# Adafruit_7seg_backpack.net
KiCad netlist of a schematic drawn in EAGLE
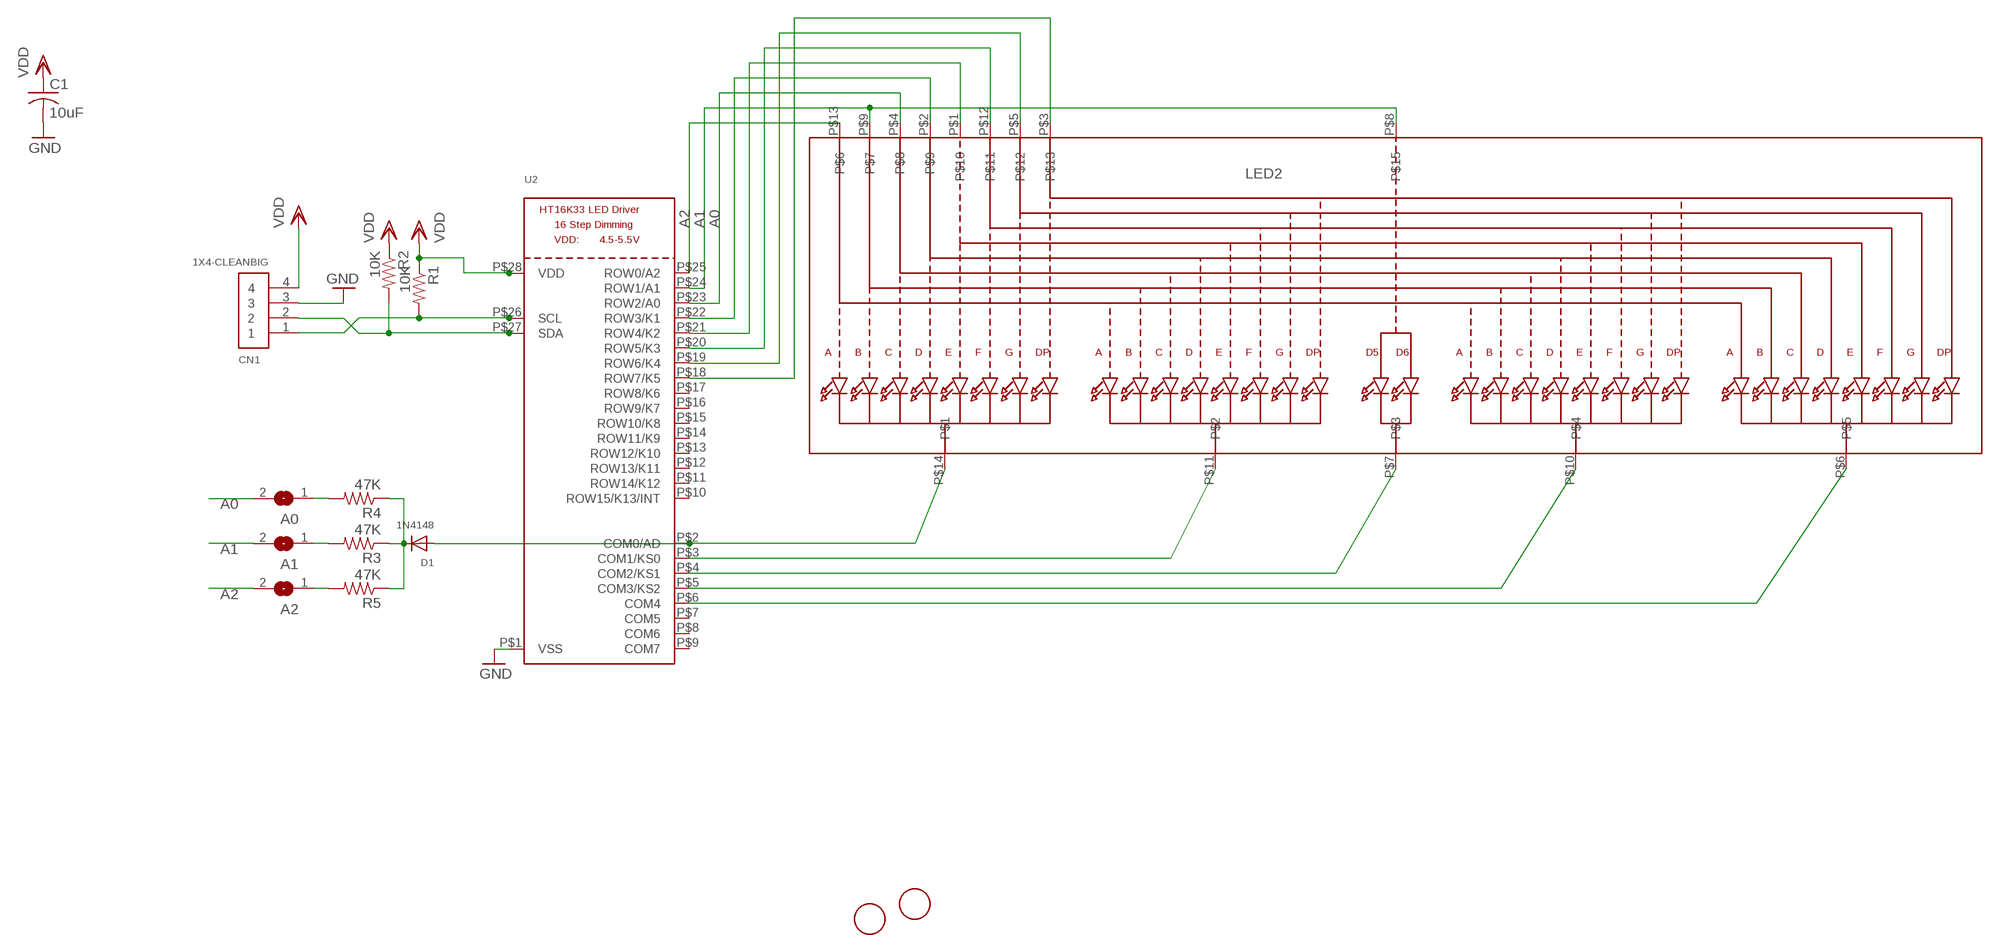
[diagram p0: schematic, sheet 1]

(export (version "E")
  (design (tool "Eeschema 10.0.6"))
  (components
    (comp (ref "A0")
      (value "SOLDERJUMPERREFLOW_NOPASTE")
      (footprint "eagle-import:SOLDERJUMPER_REFLOW_NOPASTE")
      (libsource (lib "eagle-import") (part "SOLDERJUMPERREFLOW_NOPASTE"))
    )
    (comp (ref "A1")
      (value "SOLDERJUMPERREFLOW_NOPASTE")
      (footprint "eagle-import:SOLDERJUMPER_REFLOW_NOPASTE")
      (libsource (lib "eagle-import") (part "SOLDERJUMPERREFLOW_NOPASTE"))
    )
    (comp (ref "A2")
      (value "SOLDERJUMPERREFLOW_NOPASTE")
      (footprint "eagle-import:SOLDERJUMPER_REFLOW_NOPASTE")
      (libsource (lib "eagle-import") (part "SOLDERJUMPERREFLOW_NOPASTE"))
    )
    (comp (ref "C1")
      (value "10uF")
      (footprint "eagle-import:C0805K")
      (libsource (lib "eagle-import") (part "C-USC0805K"))
    )
    (comp (ref "CN1")
      (value "1X4-CLEANBIG")
      (footprint "eagle-import:1X04-CLEANBIG")
      (libsource (lib "eagle-import") (part "1X4-CLEANBIG"))
    )
    (comp (ref "D1")
      (value "1N4148")
      (footprint "eagle-import:SOD-323F")
      (libsource (lib "eagle-import") (part "DIODESOD-323F"))
    )
    (comp (ref "LED2")
      (value "DISP_SEGMENT_4DIGIT_BL-Q56C43")
      (footprint "eagle-import:SEGMENT-BL-Q56C43")
      (libsource (lib "eagle-import") (part "DISP_SEGMENT_4DIGIT_BL-Q56C43"))
    )
    (comp (ref "R1")
      (value "10K")
      (footprint "eagle-import:R0805")
      (libsource (lib "eagle-import") (part "R-US_R0805"))
    )
    (comp (ref "R2")
      (value "10K")
      (footprint "eagle-import:R0805")
      (libsource (lib "eagle-import") (part "R-US_R0805"))
    )
    (comp (ref "R3")
      (value "47K")
      (footprint "eagle-import:R0805")
      (libsource (lib "eagle-import") (part "R-US_R0805"))
    )
    (comp (ref "R4")
      (value "47K")
      (footprint "eagle-import:R0805")
      (libsource (lib "eagle-import") (part "R-US_R0805"))
    )
    (comp (ref "R5")
      (value "47K")
      (footprint "eagle-import:R0805")
      (libsource (lib "eagle-import") (part "R-US_R0805"))
    )
    (comp (ref "U$1")
      (value "FIDUCIAL")
      (footprint "eagle-import:FIDUCIAL_1MM")
      (libsource (lib "eagle-import") (part "FIDUCIAL"))
    )
    (comp (ref "U$2")
      (value "FIDUCIAL")
      (footprint "eagle-import:FIDUCIAL_1MM")
      (libsource (lib "eagle-import") (part "FIDUCIAL"))
    )
    (comp (ref "U2")
      (value "HT16K33_SOP28")
      (footprint "eagle-import:SOP28_300MIL")
      (libsource (lib "eagle-import") (part "HT16K33_SOP28"))
    )
  )
  (nets
    (net (code "1") (name "/A0") (class "Default")
      (node (ref "A0") (pin "2") (pinfunction "2_2") (pintype "passive"))
      (node (ref "LED2") (pin "P$4") (pinfunction "P$8_P$4") (pintype "bidirectional"))
      (node (ref "U2") (pin "P$23") (pinfunction "ROW2/A0_P$23") (pintype "bidirectional"))
    )
    (net (code "2") (name "/A1") (class "Default")
      (node (ref "A1") (pin "2") (pinfunction "2_2") (pintype "passive"))
      (node (ref "LED2") (pin "P$8") (pinfunction "P$15_P$8") (pintype "bidirectional"))
      (node (ref "LED2") (pin "P$9") (pinfunction "P$7_P$9") (pintype "bidirectional"))
      (node (ref "U2") (pin "P$24") (pinfunction "ROW1/A1_P$24") (pintype "bidirectional"))
    )
    (net (code "3") (name "/A2") (class "Default")
      (node (ref "A2") (pin "2") (pinfunction "2_2") (pintype "passive"))
      (node (ref "LED2") (pin "P$13") (pinfunction "P$6_P$13") (pintype "bidirectional"))
      (node (ref "U2") (pin "P$25") (pinfunction "ROW0/A2_P$25") (pintype "bidirectional"))
    )
    (net (code "4") (name "GND") (class "Default")
      (node (ref "C1") (pin "2") (pinfunction "2_2") (pintype "passive"))
      (node (ref "CN1") (pin "3") (pinfunction "3_3") (pintype "bidirectional"))
      (node (ref "U2") (pin "P$1") (pinfunction "VSS_P$1") (pintype "bidirectional"))
    )
    (net (code "5") (name "Net-(A0-Pad1)") (class "Default")
      (node (ref "A0") (pin "1") (pinfunction "1_1") (pintype "passive"))
      (node (ref "R4") (pin "2") (pinfunction "2_2") (pintype "passive"))
    )
    (net (code "6") (name "Net-(A1-Pad1)") (class "Default")
      (node (ref "A1") (pin "1") (pinfunction "1_1") (pintype "passive"))
      (node (ref "R3") (pin "2") (pinfunction "2_2") (pintype "passive"))
    )
    (net (code "7") (name "Net-(A2-Pad1)") (class "Default")
      (node (ref "A2") (pin "1") (pinfunction "1_1") (pintype "passive"))
      (node (ref "R5") (pin "2") (pinfunction "2_2") (pintype "passive"))
    )
    (net (code "8") (name "Net-(D1-PadC)") (class "Default")
      (node (ref "D1") (pin "C") (pinfunction "C_C") (pintype "passive"))
      (node (ref "R3") (pin "1") (pinfunction "1_1") (pintype "passive"))
      (node (ref "R4") (pin "1") (pinfunction "1_1") (pintype "passive"))
      (node (ref "R5") (pin "1") (pinfunction "1_1") (pintype "passive"))
    )
    (net (code "9") (name "Net-(LED2-P$1)") (class "Default")
      (node (ref "D1") (pin "A") (pinfunction "A_A") (pintype "passive"))
      (node (ref "LED2") (pin "P$14") (pinfunction "P$1_P$14") (pintype "bidirectional"))
      (node (ref "U2") (pin "P$2") (pinfunction "COM0/AD_P$2") (pintype "bidirectional"))
    )
    (net (code "10") (name "Net-(LED2-P$2)") (class "Default")
      (node (ref "LED2") (pin "P$11") (pinfunction "P$2_P$11") (pintype "bidirectional"))
      (node (ref "U2") (pin "P$3") (pinfunction "COM1/KS0_P$3") (pintype "bidirectional"))
    )
    (net (code "11") (name "Net-(LED2-P$3)") (class "Default")
      (node (ref "LED2") (pin "P$7") (pinfunction "P$3_P$7") (pintype "bidirectional"))
      (node (ref "U2") (pin "P$4") (pinfunction "COM2/KS1_P$4") (pintype "bidirectional"))
    )
    (net (code "12") (name "Net-(LED2-P$4)") (class "Default")
      (node (ref "LED2") (pin "P$10") (pinfunction "P$4_P$10") (pintype "bidirectional"))
      (node (ref "U2") (pin "P$5") (pinfunction "COM3/KS2_P$5") (pintype "bidirectional"))
    )
    (net (code "13") (name "Net-(LED2-P$5)") (class "Default")
      (node (ref "LED2") (pin "P$6") (pinfunction "P$5_P$6") (pintype "bidirectional"))
      (node (ref "U2") (pin "P$6") (pinfunction "COM4_P$6") (pintype "bidirectional"))
    )
    (net (code "14") (name "Net-(LED2-P$9)") (class "Default")
      (node (ref "LED2") (pin "P$2") (pinfunction "P$9_P$2") (pintype "bidirectional"))
      (node (ref "U2") (pin "P$22") (pinfunction "ROW3/K1_P$22") (pintype "bidirectional"))
    )
    (net (code "15") (name "Net-(LED2-P$10)") (class "Default")
      (node (ref "LED2") (pin "P$1") (pinfunction "P$10_P$1") (pintype "bidirectional"))
      (node (ref "U2") (pin "P$21") (pinfunction "ROW4/K2_P$21") (pintype "bidirectional"))
    )
    (net (code "16") (name "Net-(LED2-P$11)") (class "Default")
      (node (ref "LED2") (pin "P$12") (pinfunction "P$11_P$12") (pintype "bidirectional"))
      (node (ref "U2") (pin "P$20") (pinfunction "ROW5/K3_P$20") (pintype "bidirectional"))
    )
    (net (code "17") (name "Net-(LED2-P$12)") (class "Default")
      (node (ref "LED2") (pin "P$5") (pinfunction "P$12_P$5") (pintype "bidirectional"))
      (node (ref "U2") (pin "P$19") (pinfunction "ROW6/K4_P$19") (pintype "bidirectional"))
    )
    (net (code "18") (name "Net-(LED2-P$13)") (class "Default")
      (node (ref "LED2") (pin "P$3") (pinfunction "P$13_P$3") (pintype "bidirectional"))
      (node (ref "U2") (pin "P$18") (pinfunction "ROW7/K5_P$18") (pintype "bidirectional"))
    )
    (net (code "19") (name "Net-(U2-SCL)") (class "Default")
      (node (ref "CN1") (pin "1") (pinfunction "1_1") (pintype "bidirectional"))
      (node (ref "R1") (pin "2") (pinfunction "2_2") (pintype "passive"))
      (node (ref "U2") (pin "P$26") (pinfunction "SCL_P$26") (pintype "bidirectional"))
    )
    (net (code "20") (name "Net-(U2-SDA)") (class "Default")
      (node (ref "CN1") (pin "2") (pinfunction "2_2") (pintype "bidirectional"))
      (node (ref "R2") (pin "2") (pinfunction "2_2") (pintype "passive"))
      (node (ref "U2") (pin "P$27") (pinfunction "SDA_P$27") (pintype "bidirectional"))
    )
    (net (code "21") (name "VDD") (class "Default")
      (node (ref "C1") (pin "1") (pinfunction "1_1") (pintype "passive"))
      (node (ref "CN1") (pin "4") (pinfunction "4_4") (pintype "bidirectional"))
      (node (ref "R1") (pin "1") (pinfunction "1_1") (pintype "passive"))
      (node (ref "R2") (pin "1") (pinfunction "1_1") (pintype "passive"))
      (node (ref "U2") (pin "P$28") (pinfunction "VDD_P$28") (pintype "bidirectional"))
    )
    (net (code "22") (name "unconnected-(U2-COM5-PadP$7)") (class "Default")
      (node (ref "U2") (pin "P$7") (pinfunction "COM5_P$7") (pintype "bidirectional"))
    )
    (net (code "23") (name "unconnected-(U2-COM6-PadP$8)") (class "Default")
      (node (ref "U2") (pin "P$8") (pinfunction "COM6_P$8") (pintype "bidirectional"))
    )
    (net (code "24") (name "unconnected-(U2-COM7-PadP$9)") (class "Default")
      (node (ref "U2") (pin "P$9") (pinfunction "COM7_P$9") (pintype "bidirectional"))
    )
    (net (code "25") (name "unconnected-(U2-ROW8{slash}K6-PadP$17)") (class "Default")
      (node (ref "U2") (pin "P$17") (pinfunction "ROW8/K6_P$17") (pintype "bidirectional"))
    )
    (net (code "26") (name "unconnected-(U2-ROW9{slash}K7-PadP$16)") (class "Default")
      (node (ref "U2") (pin "P$16") (pinfunction "ROW9/K7_P$16") (pintype "bidirectional"))
    )
    (net (code "27") (name "unconnected-(U2-ROW10{slash}K8-PadP$15)") (class "Default")
      (node (ref "U2") (pin "P$15") (pinfunction "ROW10/K8_P$15") (pintype "bidirectional"))
    )
    (net (code "28") (name "unconnected-(U2-ROW11{slash}K9-PadP$14)") (class "Default")
      (node (ref "U2") (pin "P$14") (pinfunction "ROW11/K9_P$14") (pintype "bidirectional"))
    )
    (net (code "29") (name "unconnected-(U2-ROW12{slash}K10-PadP$13)") (class "Default")
      (node (ref "U2") (pin "P$13") (pinfunction "ROW12/K10_P$13") (pintype "bidirectional"))
    )
    (net (code "30") (name "unconnected-(U2-ROW13{slash}K11-PadP$12)") (class "Default")
      (node (ref "U2") (pin "P$12") (pinfunction "ROW13/K11_P$12") (pintype "bidirectional"))
    )
    (net (code "31") (name "unconnected-(U2-ROW14{slash}K12-PadP$11)") (class "Default")
      (node (ref "U2") (pin "P$11") (pinfunction "ROW14/K12_P$11") (pintype "bidirectional"))
    )
    (net (code "32") (name "unconnected-(U2-ROW15{slash}K13{slash}INT-PadP$10)") (class "Default")
      (node (ref "U2") (pin "P$10") (pinfunction "ROW15/K13/INT_P$10") (pintype "bidirectional"))
    )
  )
)
